# terminal.net
KiCad netlist of a schematic drawn in EAGLE
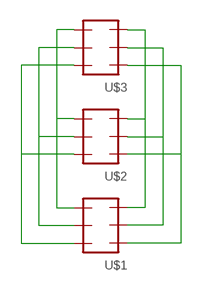
[diagram p0: schematic, sheet 1]

(export (version "E")
  (design (tool "Eeschema 10.0.6"))
  (components
    (comp (ref "U$1")
      (value "PIN_HEADER_32")
      (footprint "eagle-import:PIN_HEADER_3_2")
      (libsource (lib "eagle-import") (part "PIN_HEADER_32"))
    )
    (comp (ref "U$2")
      (value "PIN_HEADER_32")
      (footprint "eagle-import:PIN_HEADER_3_2")
      (libsource (lib "eagle-import") (part "PIN_HEADER_32"))
    )
    (comp (ref "U$3")
      (value "PIN_HEADER_32")
      (footprint "eagle-import:PIN_HEADER_3_2")
      (libsource (lib "eagle-import") (part "PIN_HEADER_32"))
    )
  )
  (nets
    (net (code "1") (name "Net-(U$1-1)") (class "Default")
      (node (ref "U$1") (pin "P$1") (pinfunction "1_P$1") (pintype "bidirectional"))
      (node (ref "U$2") (pin "P$1") (pinfunction "1_P$1") (pintype "bidirectional"))
      (node (ref "U$3") (pin "P$1") (pinfunction "1_P$1") (pintype "bidirectional"))
    )
    (net (code "2") (name "Net-(U$1-2)") (class "Default")
      (node (ref "U$1") (pin "P$2") (pinfunction "2_P$2") (pintype "bidirectional"))
      (node (ref "U$2") (pin "P$2") (pinfunction "2_P$2") (pintype "bidirectional"))
      (node (ref "U$3") (pin "P$2") (pinfunction "2_P$2") (pintype "bidirectional"))
    )
    (net (code "3") (name "Net-(U$1-3)") (class "Default")
      (node (ref "U$1") (pin "P$3") (pinfunction "3_P$3") (pintype "bidirectional"))
      (node (ref "U$2") (pin "P$3") (pinfunction "3_P$3") (pintype "bidirectional"))
      (node (ref "U$3") (pin "P$3") (pinfunction "3_P$3") (pintype "bidirectional"))
    )
    (net (code "4") (name "Net-(U$1-4)") (class "Default")
      (node (ref "U$1") (pin "P$4") (pinfunction "4_P$4") (pintype "bidirectional"))
      (node (ref "U$2") (pin "P$4") (pinfunction "4_P$4") (pintype "bidirectional"))
      (node (ref "U$3") (pin "P$4") (pinfunction "4_P$4") (pintype "bidirectional"))
    )
    (net (code "5") (name "Net-(U$1-5)") (class "Default")
      (node (ref "U$1") (pin "P$5") (pinfunction "5_P$5") (pintype "bidirectional"))
      (node (ref "U$2") (pin "P$5") (pinfunction "5_P$5") (pintype "bidirectional"))
      (node (ref "U$3") (pin "P$5") (pinfunction "5_P$5") (pintype "bidirectional"))
    )
    (net (code "6") (name "Net-(U$1-6)") (class "Default")
      (node (ref "U$1") (pin "P$6") (pinfunction "6_P$6") (pintype "bidirectional"))
      (node (ref "U$2") (pin "P$6") (pinfunction "6_P$6") (pintype "bidirectional"))
      (node (ref "U$3") (pin "P$6") (pinfunction "6_P$6") (pintype "bidirectional"))
    )
  )
)
